# PushButton.net
KiCad netlist of a schematic drawn in Altium Designer
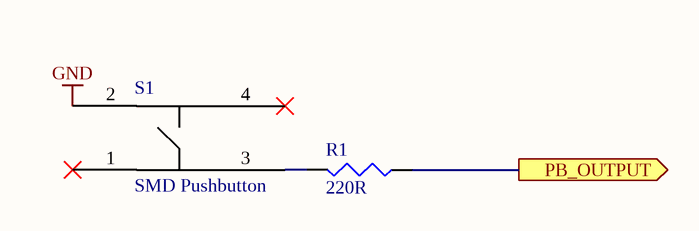
[diagram p0: PushButton.SchDoc]

(export (version "E")
  (design (tool "Eeschema 10.0.6"))
  (components
    (comp (ref "R1")
      (value "220R")
      (footprint "6-0805_N")
      (description "Resistor, 0.25W")
      (fields (field (name "Comment") "0805"))
      (libsource (lib "Miscellaneous Devices") (part "Res3"))
    )
    (comp (ref "S1")
      (value "SMD Pushbutton")
      (footprint "SMD_PB")
      (libsource (lib "Switches") (part "SMD_PB"))
    )
  )
  (nets
    (net (code "1") (name "/PB_OUTPUT") (class "Default")
      (node (ref "R1") (pin "1") (pinfunction "1_1") (pintype "passive"))
    )
    (net (code "2") (name "GND") (class "Default")
      (node (ref "S1") (pin "2") (pinfunction "2_2") (pintype "passive"))
    )
    (net (code "3") (name "Net-(R1-Pad2)") (class "Default")
      (node (ref "R1") (pin "2") (pinfunction "2_2") (pintype "passive"))
      (node (ref "S1") (pin "3") (pinfunction "3_3") (pintype "passive"))
    )
    (net (code "4") (name "unconnected-(S1-Pad1)") (class "Default")
      (node (ref "S1") (pin "1") (pinfunction "1_1") (pintype "passive+no_connect"))
    )
    (net (code "5") (name "unconnected-(S1-Pad4)") (class "Default")
      (node (ref "S1") (pin "4") (pinfunction "4_4") (pintype "passive+no_connect"))
    )
  )
)
